# photocell.net
KiCad netlist of a schematic drawn in EAGLE
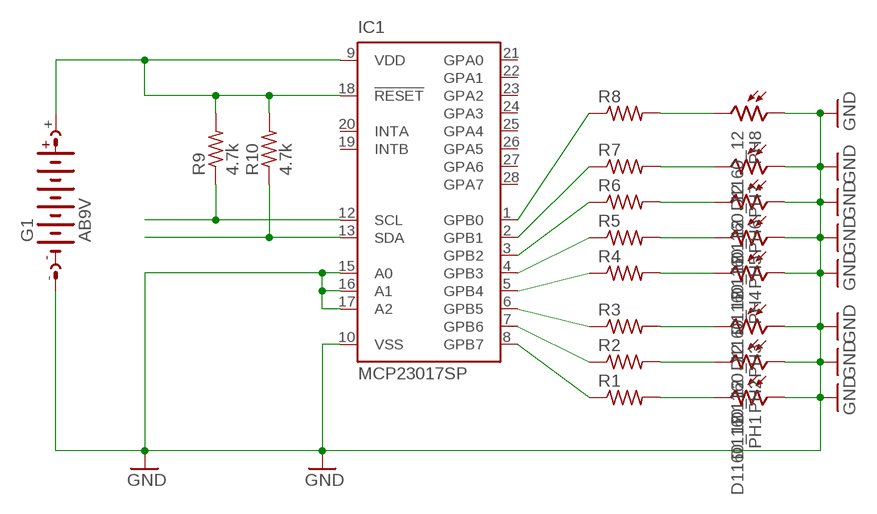
[diagram p0: schematic, sheet 1]

(export (version "E")
  (design (tool "Eeschema 10.0.6"))
  (components
    (comp (ref "G1")
      (value "AB9V")
      (footprint "eagle-import:AB9V")
      (libsource (lib "eagle-import") (part "AB9V"))
    )
    (comp (ref "IC1")
      (value "MCP23017SP")
      (footprint "eagle-import:DIL28-3")
      (fields (field (name "MF") "MICROCHIP") (field (name "MPN") "MCP23017-E/SP"))
      (libsource (lib "eagle-import") (part "MCP23017SP"))
    )
    (comp (ref "PH1")
      (value "D1160_12")
      (footprint "eagle-import:D11XX")
      (libsource (lib "eagle-import") (part "D1160_12"))
    )
    (comp (ref "PH2")
      (value "D1160_12")
      (footprint "eagle-import:D11XX")
      (libsource (lib "eagle-import") (part "D1160_12"))
    )
    (comp (ref "PH3")
      (value "D1160_12")
      (footprint "eagle-import:D11XX")
      (libsource (lib "eagle-import") (part "D1160_12"))
    )
    (comp (ref "PH4")
      (value "D1160_12")
      (footprint "eagle-import:D11XX")
      (libsource (lib "eagle-import") (part "D1160_12"))
    )
    (comp (ref "PH5")
      (value "D1160_12")
      (footprint "eagle-import:D11XX")
      (libsource (lib "eagle-import") (part "D1160_12"))
    )
    (comp (ref "PH6")
      (value "D1160_12")
      (footprint "eagle-import:D11XX")
      (libsource (lib "eagle-import") (part "D1160_12"))
    )
    (comp (ref "PH7")
      (value "D1160_12")
      (footprint "eagle-import:D11XX")
      (libsource (lib "eagle-import") (part "D1160_12"))
    )
    (comp (ref "PH8")
      (value "D1160_12")
      (footprint "eagle-import:D11XX")
      (libsource (lib "eagle-import") (part "D1160_12"))
    )
    (comp (ref "R1")
      (value "R-US_0204/7")
      (footprint "eagle-import:0204_7")
      (libsource (lib "eagle-import") (part "R-US_0204/7"))
    )
    (comp (ref "R2")
      (value "R-US_0204/7")
      (footprint "eagle-import:0204_7")
      (libsource (lib "eagle-import") (part "R-US_0204/7"))
    )
    (comp (ref "R3")
      (value "R-US_0204/7")
      (footprint "eagle-import:0204_7")
      (libsource (lib "eagle-import") (part "R-US_0204/7"))
    )
    (comp (ref "R4")
      (value "R-US_0204/7")
      (footprint "eagle-import:0204_7")
      (libsource (lib "eagle-import") (part "R-US_0204/7"))
    )
    (comp (ref "R5")
      (value "R-US_0204/7")
      (footprint "eagle-import:0204_7")
      (libsource (lib "eagle-import") (part "R-US_0204/7"))
    )
    (comp (ref "R6")
      (value "R-US_0204/7")
      (footprint "eagle-import:0204_7")
      (libsource (lib "eagle-import") (part "R-US_0204/7"))
    )
    (comp (ref "R7")
      (value "R-US_0204/7")
      (footprint "eagle-import:0204_7")
      (libsource (lib "eagle-import") (part "R-US_0204/7"))
    )
    (comp (ref "R8")
      (value "R-US_0204/7")
      (footprint "eagle-import:0204_7")
      (libsource (lib "eagle-import") (part "R-US_0204/7"))
    )
    (comp (ref "R9")
      (value "4.7k")
      (footprint "eagle-import:0204_7")
      (libsource (lib "eagle-import") (part "R-US_0204/7"))
    )
    (comp (ref "R10")
      (value "4.7k")
      (footprint "eagle-import:0204_7")
      (libsource (lib "eagle-import") (part "R-US_0204/7"))
    )
  )
  (nets
    (net (code "1") (name "GND") (class "Default")
      (node (ref "G1") (pin "-") (pinfunction "-_-") (pintype "passive"))
      (node (ref "IC1") (pin "10") (pinfunction "VSS_10") (pintype "power_in"))
      (node (ref "IC1") (pin "15") (pinfunction "A0_15") (pintype "input"))
      (node (ref "IC1") (pin "16") (pinfunction "A1_16") (pintype "input"))
      (node (ref "IC1") (pin "17") (pinfunction "A2_17") (pintype "input"))
      (node (ref "PH1") (pin "1") (pinfunction "1_1") (pintype "passive"))
      (node (ref "PH2") (pin "1") (pinfunction "1_1") (pintype "passive"))
      (node (ref "PH3") (pin "1") (pinfunction "1_1") (pintype "passive"))
      (node (ref "PH4") (pin "1") (pinfunction "1_1") (pintype "passive"))
      (node (ref "PH5") (pin "1") (pinfunction "1_1") (pintype "passive"))
      (node (ref "PH6") (pin "1") (pinfunction "1_1") (pintype "passive"))
      (node (ref "PH7") (pin "1") (pinfunction "1_1") (pintype "passive"))
      (node (ref "PH8") (pin "1") (pinfunction "1_1") (pintype "passive"))
    )
    (net (code "2") (name "Net-(IC1-GPB0)") (class "Default")
      (node (ref "IC1") (pin "1") (pinfunction "GPB0_1") (pintype "bidirectional"))
      (node (ref "R8") (pin "1") (pinfunction "1_1") (pintype "passive"))
    )
    (net (code "3") (name "Net-(IC1-GPB1)") (class "Default")
      (node (ref "IC1") (pin "2") (pinfunction "GPB1_2") (pintype "bidirectional"))
      (node (ref "R7") (pin "1") (pinfunction "1_1") (pintype "passive"))
    )
    (net (code "4") (name "Net-(IC1-GPB2)") (class "Default")
      (node (ref "IC1") (pin "3") (pinfunction "GPB2_3") (pintype "bidirectional"))
      (node (ref "R6") (pin "1") (pinfunction "1_1") (pintype "passive"))
    )
    (net (code "5") (name "Net-(IC1-GPB3)") (class "Default")
      (node (ref "IC1") (pin "4") (pinfunction "GPB3_4") (pintype "bidirectional"))
      (node (ref "R5") (pin "1") (pinfunction "1_1") (pintype "passive"))
    )
    (net (code "6") (name "Net-(IC1-GPB4)") (class "Default")
      (node (ref "IC1") (pin "5") (pinfunction "GPB4_5") (pintype "bidirectional"))
      (node (ref "R4") (pin "1") (pinfunction "1_1") (pintype "passive"))
    )
    (net (code "7") (name "Net-(IC1-GPB5)") (class "Default")
      (node (ref "IC1") (pin "6") (pinfunction "GPB5_6") (pintype "bidirectional"))
      (node (ref "R3") (pin "1") (pinfunction "1_1") (pintype "passive"))
    )
    (net (code "8") (name "Net-(IC1-GPB6)") (class "Default")
      (node (ref "IC1") (pin "7") (pinfunction "GPB6_7") (pintype "bidirectional"))
      (node (ref "R2") (pin "1") (pinfunction "1_1") (pintype "passive"))
    )
    (net (code "9") (name "Net-(IC1-GPB7)") (class "Default")
      (node (ref "IC1") (pin "8") (pinfunction "GPB7_8") (pintype "bidirectional"))
      (node (ref "R1") (pin "1") (pinfunction "1_1") (pintype "passive"))
    )
    (net (code "10") (name "Net-(IC1-SCL)") (class "Default")
      (node (ref "IC1") (pin "12") (pinfunction "SCL_12") (pintype "input"))
      (node (ref "R9") (pin "1") (pinfunction "1_1") (pintype "passive"))
    )
    (net (code "11") (name "Net-(IC1-SDA)") (class "Default")
      (node (ref "IC1") (pin "13") (pinfunction "SDA_13") (pintype "bidirectional"))
      (node (ref "R10") (pin "1") (pinfunction "1_1") (pintype "passive"))
    )
    (net (code "12") (name "Net-(IC1-VDD)") (class "Default")
      (node (ref "G1") (pin "+") (pinfunction "+_+") (pintype "passive"))
      (node (ref "IC1") (pin "18") (pinfunction "~{RESET}_18") (pintype "input"))
      (node (ref "IC1") (pin "9") (pinfunction "VDD_9") (pintype "power_in"))
      (node (ref "R10") (pin "2") (pinfunction "2_2") (pintype "passive"))
      (node (ref "R9") (pin "2") (pinfunction "2_2") (pintype "passive"))
    )
    (net (code "13") (name "Net-(PH1-Pad2)") (class "Default")
      (node (ref "PH1") (pin "2") (pinfunction "2_2") (pintype "passive"))
      (node (ref "R1") (pin "2") (pinfunction "2_2") (pintype "passive"))
    )
    (net (code "14") (name "Net-(PH2-Pad2)") (class "Default")
      (node (ref "PH2") (pin "2") (pinfunction "2_2") (pintype "passive"))
      (node (ref "R2") (pin "2") (pinfunction "2_2") (pintype "passive"))
    )
    (net (code "15") (name "Net-(PH3-Pad2)") (class "Default")
      (node (ref "PH3") (pin "2") (pinfunction "2_2") (pintype "passive"))
      (node (ref "R3") (pin "2") (pinfunction "2_2") (pintype "passive"))
    )
    (net (code "16") (name "Net-(PH4-Pad2)") (class "Default")
      (node (ref "PH4") (pin "2") (pinfunction "2_2") (pintype "passive"))
      (node (ref "R4") (pin "2") (pinfunction "2_2") (pintype "passive"))
    )
    (net (code "17") (name "Net-(PH5-Pad2)") (class "Default")
      (node (ref "PH5") (pin "2") (pinfunction "2_2") (pintype "passive"))
      (node (ref "R5") (pin "2") (pinfunction "2_2") (pintype "passive"))
    )
    (net (code "18") (name "Net-(PH6-Pad2)") (class "Default")
      (node (ref "PH6") (pin "2") (pinfunction "2_2") (pintype "passive"))
      (node (ref "R6") (pin "2") (pinfunction "2_2") (pintype "passive"))
    )
    (net (code "19") (name "Net-(PH7-Pad2)") (class "Default")
      (node (ref "PH7") (pin "2") (pinfunction "2_2") (pintype "passive"))
      (node (ref "R7") (pin "2") (pinfunction "2_2") (pintype "passive"))
    )
    (net (code "20") (name "Net-(PH8-Pad2)") (class "Default")
      (node (ref "PH8") (pin "2") (pinfunction "2_2") (pintype "passive"))
      (node (ref "R8") (pin "2") (pinfunction "2_2") (pintype "passive"))
    )
    (net (code "21") (name "unconnected-(IC1-GPA0-Pad21)") (class "Default")
      (node (ref "IC1") (pin "21") (pinfunction "GPA0_21") (pintype "bidirectional"))
    )
    (net (code "22") (name "unconnected-(IC1-GPA1-Pad22)") (class "Default")
      (node (ref "IC1") (pin "22") (pinfunction "GPA1_22") (pintype "bidirectional"))
    )
    (net (code "23") (name "unconnected-(IC1-GPA2-Pad23)") (class "Default")
      (node (ref "IC1") (pin "23") (pinfunction "GPA2_23") (pintype "bidirectional"))
    )
    (net (code "24") (name "unconnected-(IC1-GPA3-Pad24)") (class "Default")
      (node (ref "IC1") (pin "24") (pinfunction "GPA3_24") (pintype "bidirectional"))
    )
    (net (code "25") (name "unconnected-(IC1-GPA4-Pad25)") (class "Default")
      (node (ref "IC1") (pin "25") (pinfunction "GPA4_25") (pintype "bidirectional"))
    )
    (net (code "26") (name "unconnected-(IC1-GPA5-Pad26)") (class "Default")
      (node (ref "IC1") (pin "26") (pinfunction "GPA5_26") (pintype "bidirectional"))
    )
    (net (code "27") (name "unconnected-(IC1-GPA6-Pad27)") (class "Default")
      (node (ref "IC1") (pin "27") (pinfunction "GPA6_27") (pintype "bidirectional"))
    )
    (net (code "28") (name "unconnected-(IC1-GPA7-Pad28)") (class "Default")
      (node (ref "IC1") (pin "28") (pinfunction "GPA7_28") (pintype "bidirectional"))
    )
    (net (code "29") (name "unconnected-(IC1-INTA-Pad20)") (class "Default")
      (node (ref "IC1") (pin "20") (pinfunction "INTA_20") (pintype "output"))
    )
    (net (code "30") (name "unconnected-(IC1-INTB-Pad19)") (class "Default")
      (node (ref "IC1") (pin "19") (pinfunction "INTB_19") (pintype "output"))
    )
  )
)
